# comparator.net
KiCad netlist of a schematic drawn in EAGLE
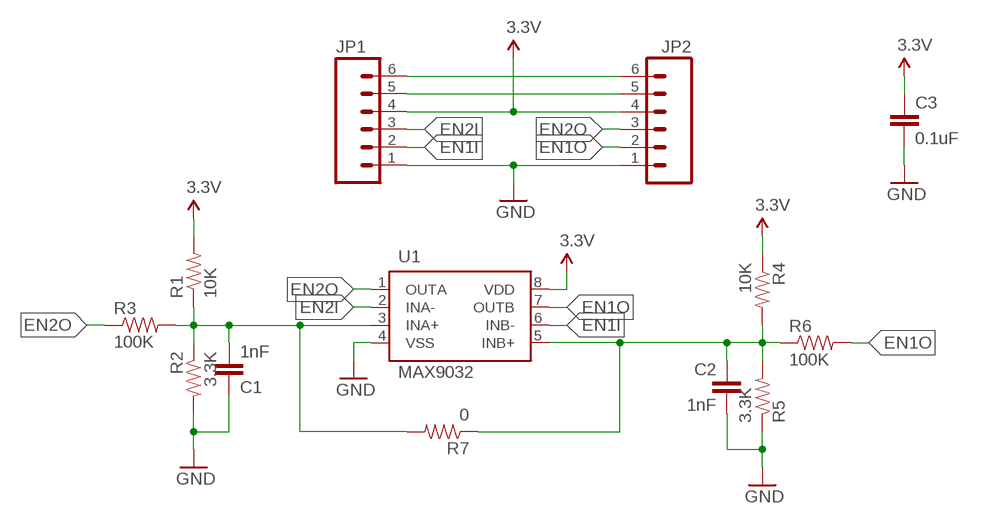
[diagram p0: schematic, sheet 1]

(export (version "E")
  (design (tool "Eeschema 10.0.6"))
  (components
    (comp (ref "C1")
      (value "1nF")
      (footprint "eagle-import:0603-CAP")
      (libsource (lib "eagle-import") (part "CAP0603-CAP"))
    )
    (comp (ref "C2")
      (value "1nF")
      (footprint "eagle-import:0603-CAP")
      (libsource (lib "eagle-import") (part "CAP0603-CAP"))
    )
    (comp (ref "C3")
      (value "0.1uF")
      (footprint "eagle-import:0603-CAP")
      (libsource (lib "eagle-import") (part "CAP0603-CAP"))
    )
    (comp (ref "JP1")
      (value "M06SMDF")
      (footprint "eagle-import:1X06-SMD-FEMALE")
      (libsource (lib "eagle-import") (part "M06SMDF"))
    )
    (comp (ref "JP2")
      (value "M06LOCK")
      (footprint "eagle-import:1X06_LOCK")
      (libsource (lib "eagle-import") (part "M06LOCK"))
    )
    (comp (ref "R1")
      (value "10K")
      (footprint "eagle-import:0603-RES")
      (libsource (lib "eagle-import") (part "RESISTOR0603"))
    )
    (comp (ref "R2")
      (value "3.3K")
      (footprint "eagle-import:0603-RES")
      (libsource (lib "eagle-import") (part "RESISTOR0603"))
    )
    (comp (ref "R3")
      (value "100K")
      (footprint "eagle-import:0603-RES")
      (libsource (lib "eagle-import") (part "RESISTOR0603"))
    )
    (comp (ref "R4")
      (value "10K")
      (footprint "eagle-import:0603-RES")
      (libsource (lib "eagle-import") (part "RESISTOR0603"))
    )
    (comp (ref "R5")
      (value "3.3K")
      (footprint "eagle-import:0603-RES")
      (libsource (lib "eagle-import") (part "RESISTOR0603"))
    )
    (comp (ref "R6")
      (value "100K")
      (footprint "eagle-import:0603-RES")
      (libsource (lib "eagle-import") (part "RESISTOR0603"))
    )
    (comp (ref "R7")
      (value "0")
      (footprint "eagle-import:0603-RES")
      (libsource (lib "eagle-import") (part "RESISTOR0603"))
    )
    (comp (ref "U1")
      (value "MAX9032")
      (footprint "eagle-import:SOT23-8")
      (libsource (lib "eagle-import") (part "MAX9032"))
    )
  )
  (nets
    (net (code "1") (name "3.3V") (class "Default")
      (node (ref "C3") (pin "1") (pinfunction "1_1") (pintype "passive"))
      (node (ref "JP1") (pin "4") (pinfunction "4_4") (pintype "passive"))
      (node (ref "JP2") (pin "4") (pinfunction "4_4") (pintype "passive"))
      (node (ref "R1") (pin "2") (pinfunction "2_2") (pintype "passive"))
      (node (ref "R4") (pin "1") (pinfunction "1_1") (pintype "passive"))
      (node (ref "U1") (pin "8") (pinfunction "VDD_8") (pintype "bidirectional"))
    )
    (net (code "2") (name "EN1I") (class "Default")
      (node (ref "JP1") (pin "2") (pinfunction "2_2") (pintype "passive"))
      (node (ref "U1") (pin "6") (pinfunction "INB-_6") (pintype "bidirectional"))
    )
    (net (code "3") (name "EN1O") (class "Default")
      (node (ref "JP2") (pin "2") (pinfunction "2_2") (pintype "passive"))
      (node (ref "R6") (pin "2") (pinfunction "2_2") (pintype "passive"))
      (node (ref "U1") (pin "7") (pinfunction "OUTB_7") (pintype "bidirectional"))
    )
    (net (code "4") (name "EN2I") (class "Default")
      (node (ref "JP1") (pin "3") (pinfunction "3_3") (pintype "passive"))
      (node (ref "U1") (pin "2") (pinfunction "INA-_2") (pintype "bidirectional"))
    )
    (net (code "5") (name "EN2O") (class "Default")
      (node (ref "JP2") (pin "3") (pinfunction "3_3") (pintype "passive"))
      (node (ref "R3") (pin "1") (pinfunction "1_1") (pintype "passive"))
      (node (ref "U1") (pin "1") (pinfunction "OUTA_1") (pintype "bidirectional"))
    )
    (net (code "6") (name "GND") (class "Default")
      (node (ref "C1") (pin "1") (pinfunction "1_1") (pintype "passive"))
      (node (ref "C2") (pin "2") (pinfunction "2_2") (pintype "passive"))
      (node (ref "C3") (pin "2") (pinfunction "2_2") (pintype "passive"))
      (node (ref "JP1") (pin "1") (pinfunction "1_1") (pintype "passive"))
      (node (ref "JP2") (pin "1") (pinfunction "1_1") (pintype "passive"))
      (node (ref "R2") (pin "2") (pinfunction "2_2") (pintype "passive"))
      (node (ref "R5") (pin "1") (pinfunction "1_1") (pintype "passive"))
      (node (ref "U1") (pin "4") (pinfunction "VSS_4") (pintype "bidirectional"))
    )
    (net (code "7") (name "Net-(JP1-Pad5)") (class "Default")
      (node (ref "JP1") (pin "5") (pinfunction "5_5") (pintype "passive"))
      (node (ref "JP2") (pin "5") (pinfunction "5_5") (pintype "passive"))
    )
    (net (code "8") (name "Net-(JP1-Pad6)") (class "Default")
      (node (ref "JP1") (pin "6") (pinfunction "6_6") (pintype "passive"))
      (node (ref "JP2") (pin "6") (pinfunction "6_6") (pintype "passive"))
    )
    (net (code "9") (name "Net-(U1-INA+)") (class "Default")
      (node (ref "C1") (pin "2") (pinfunction "2_2") (pintype "passive"))
      (node (ref "R1") (pin "1") (pinfunction "1_1") (pintype "passive"))
      (node (ref "R2") (pin "1") (pinfunction "1_1") (pintype "passive"))
      (node (ref "R3") (pin "2") (pinfunction "2_2") (pintype "passive"))
      (node (ref "R7") (pin "2") (pinfunction "2_2") (pintype "passive"))
      (node (ref "U1") (pin "3") (pinfunction "INA+_3") (pintype "bidirectional"))
    )
    (net (code "10") (name "Net-(U1-INB+)") (class "Default")
      (node (ref "C2") (pin "1") (pinfunction "1_1") (pintype "passive"))
      (node (ref "R4") (pin "2") (pinfunction "2_2") (pintype "passive"))
      (node (ref "R5") (pin "2") (pinfunction "2_2") (pintype "passive"))
      (node (ref "R6") (pin "1") (pinfunction "1_1") (pintype "passive"))
      (node (ref "R7") (pin "1") (pinfunction "1_1") (pintype "passive"))
      (node (ref "U1") (pin "5") (pinfunction "INB+_5") (pintype "bidirectional"))
    )
  )
)
